# EIB64-ST4-Multi.net
KiCad netlist of a schematic drawn in EAGLE
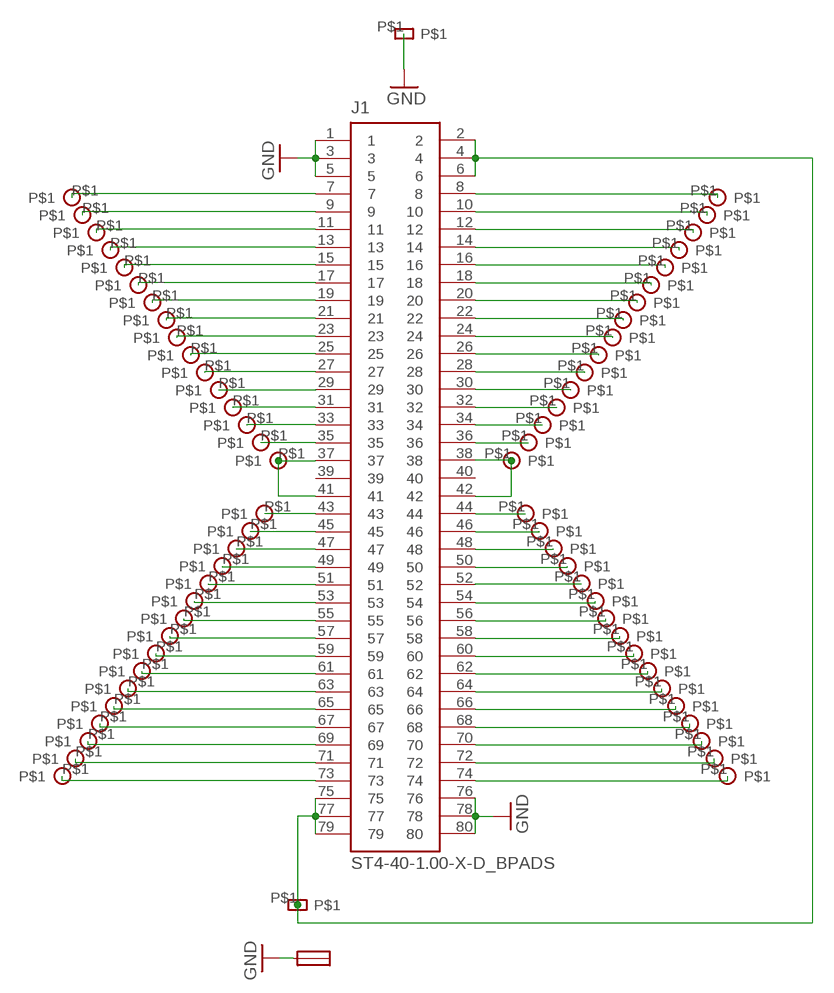
[diagram p0: schematic, sheet 1]

(export (version "E")
  (design (tool "Eeschema 10.0.6"))
  (components
    (comp (ref "J1")
      (value "ST4-40-1.00-X-D_BPADS")
      (footprint "eagle-import:ST4-40-1.00-X-D_BPADS")
      (libsource (lib "eagle-import") (part "ST4-40-1.00-X-D_BPADS"))
    )
    (comp (ref "U$1")
      (value "EIB-GND-HOLE-PAD-SMALL")
      (footprint "eagle-import:EIB-GND-HOLE-PAD-SMALL")
      (libsource (lib "eagle-import") (part "EIB-GND-HOLE-PAD-SMALL"))
    )
    (comp (ref "U$2")
      (value "JMP-PAD-SMALL")
      (footprint "eagle-import:JMP-PAD-SMALL")
      (libsource (lib "eagle-import") (part "JMP-PAD-SMALL"))
    )
    (comp (ref "U$3")
      (value "EIB-GND-HOLE-PAD-SMALL")
      (footprint "eagle-import:EIB-GND-HOLE-PAD-SMALL")
      (libsource (lib "eagle-import") (part "EIB-GND-HOLE-PAD-SMALL"))
    )
    (comp (ref "U$5")
      (value "EIB-TETRODE-HOLE-RS-PAD")
      (footprint "eagle-import:EIB-TETRODE-HOLE-RS-PAD")
      (libsource (lib "eagle-import") (part "EIB-TETRODE-HOLE-RS-PAD"))
    )
    (comp (ref "U$6")
      (value "EIB-TETRODE-HOLE-RS-PAD")
      (footprint "eagle-import:EIB-TETRODE-HOLE-RS-PAD")
      (libsource (lib "eagle-import") (part "EIB-TETRODE-HOLE-RS-PAD"))
    )
    (comp (ref "U$7")
      (value "EIB-TETRODE-HOLE-RS-PAD")
      (footprint "eagle-import:EIB-TETRODE-HOLE-RS-PAD")
      (libsource (lib "eagle-import") (part "EIB-TETRODE-HOLE-RS-PAD"))
    )
    (comp (ref "U$8")
      (value "EIB-TETRODE-HOLE-RS-PAD")
      (footprint "eagle-import:EIB-TETRODE-HOLE-RS-PAD")
      (libsource (lib "eagle-import") (part "EIB-TETRODE-HOLE-RS-PAD"))
    )
    (comp (ref "U$9")
      (value "EIB-TETRODE-HOLE-RS-PAD")
      (footprint "eagle-import:EIB-TETRODE-HOLE-RS-PAD")
      (libsource (lib "eagle-import") (part "EIB-TETRODE-HOLE-RS-PAD"))
    )
    (comp (ref "U$10")
      (value "EIB-TETRODE-HOLE-RS-PAD")
      (footprint "eagle-import:EIB-TETRODE-HOLE-RS-PAD")
      (libsource (lib "eagle-import") (part "EIB-TETRODE-HOLE-RS-PAD"))
    )
    (comp (ref "U$11")
      (value "EIB-TETRODE-HOLE-RS-PAD")
      (footprint "eagle-import:EIB-TETRODE-HOLE-RS-PAD")
      (libsource (lib "eagle-import") (part "EIB-TETRODE-HOLE-RS-PAD"))
    )
    (comp (ref "U$12")
      (value "EIB-TETRODE-HOLE-RS-PAD")
      (footprint "eagle-import:EIB-TETRODE-HOLE-RS-PAD")
      (libsource (lib "eagle-import") (part "EIB-TETRODE-HOLE-RS-PAD"))
    )
    (comp (ref "U$13")
      (value "EIB-TETRODE-HOLE-RS-PAD")
      (footprint "eagle-import:EIB-TETRODE-HOLE-RS-PAD")
      (libsource (lib "eagle-import") (part "EIB-TETRODE-HOLE-RS-PAD"))
    )
    (comp (ref "U$14")
      (value "EIB-TETRODE-HOLE-RS-PAD")
      (footprint "eagle-import:EIB-TETRODE-HOLE-RS-PAD")
      (libsource (lib "eagle-import") (part "EIB-TETRODE-HOLE-RS-PAD"))
    )
    (comp (ref "U$15")
      (value "EIB-TETRODE-HOLE-RS-PAD")
      (footprint "eagle-import:EIB-TETRODE-HOLE-RS-PAD")
      (libsource (lib "eagle-import") (part "EIB-TETRODE-HOLE-RS-PAD"))
    )
    (comp (ref "U$16")
      (value "EIB-TETRODE-HOLE-RS-PAD")
      (footprint "eagle-import:EIB-TETRODE-HOLE-RS-PAD")
      (libsource (lib "eagle-import") (part "EIB-TETRODE-HOLE-RS-PAD"))
    )
    (comp (ref "U$17")
      (value "EIB-TETRODE-HOLE-RS-PAD")
      (footprint "eagle-import:EIB-TETRODE-HOLE-RS-PAD")
      (libsource (lib "eagle-import") (part "EIB-TETRODE-HOLE-RS-PAD"))
    )
    (comp (ref "U$18")
      (value "EIB-TETRODE-HOLE-RS-PAD")
      (footprint "eagle-import:EIB-TETRODE-HOLE-RS-PAD")
      (libsource (lib "eagle-import") (part "EIB-TETRODE-HOLE-RS-PAD"))
    )
    (comp (ref "U$19")
      (value "EIB-TETRODE-HOLE-RS-PAD")
      (footprint "eagle-import:EIB-TETRODE-HOLE-RS-PAD")
      (libsource (lib "eagle-import") (part "EIB-TETRODE-HOLE-RS-PAD"))
    )
    (comp (ref "U$20")
      (value "EIB-TETRODE-HOLE-RS-PAD")
      (footprint "eagle-import:EIB-TETRODE-HOLE-RS-PAD")
      (libsource (lib "eagle-import") (part "EIB-TETRODE-HOLE-RS-PAD"))
    )
    (comp (ref "U$21")
      (value "EIB-TETRODE-HOLE-RS-PAD")
      (footprint "eagle-import:EIB-TETRODE-HOLE-RS-PAD")
      (libsource (lib "eagle-import") (part "EIB-TETRODE-HOLE-RS-PAD"))
    )
    (comp (ref "U$22")
      (value "EIB-TETRODE-HOLE-RS-PAD")
      (footprint "eagle-import:EIB-TETRODE-HOLE-RS-PAD")
      (libsource (lib "eagle-import") (part "EIB-TETRODE-HOLE-RS-PAD"))
    )
    (comp (ref "U$23")
      (value "EIB-TETRODE-HOLE-RS-PAD")
      (footprint "eagle-import:EIB-TETRODE-HOLE-RS-PAD")
      (libsource (lib "eagle-import") (part "EIB-TETRODE-HOLE-RS-PAD"))
    )
    (comp (ref "U$24")
      (value "EIB-TETRODE-HOLE-RS-PAD")
      (footprint "eagle-import:EIB-TETRODE-HOLE-RS-PAD")
      (libsource (lib "eagle-import") (part "EIB-TETRODE-HOLE-RS-PAD"))
    )
    (comp (ref "U$25")
      (value "EIB-TETRODE-HOLE-RS-PAD")
      (footprint "eagle-import:EIB-TETRODE-HOLE-RS-PAD")
      (libsource (lib "eagle-import") (part "EIB-TETRODE-HOLE-RS-PAD"))
    )
    (comp (ref "U$26")
      (value "EIB-TETRODE-HOLE-RS-PAD")
      (footprint "eagle-import:EIB-TETRODE-HOLE-RS-PAD")
      (libsource (lib "eagle-import") (part "EIB-TETRODE-HOLE-RS-PAD"))
    )
    (comp (ref "U$27")
      (value "EIB-TETRODE-HOLE-RS-PAD")
      (footprint "eagle-import:EIB-TETRODE-HOLE-RS-PAD")
      (libsource (lib "eagle-import") (part "EIB-TETRODE-HOLE-RS-PAD"))
    )
    (comp (ref "U$28")
      (value "EIB-TETRODE-HOLE-RS-PAD")
      (footprint "eagle-import:EIB-TETRODE-HOLE-RS-PAD")
      (libsource (lib "eagle-import") (part "EIB-TETRODE-HOLE-RS-PAD"))
    )
    (comp (ref "U$29")
      (value "EIB-TETRODE-HOLE-RS-PAD")
      (footprint "eagle-import:EIB-TETRODE-HOLE-RS-PAD")
      (libsource (lib "eagle-import") (part "EIB-TETRODE-HOLE-RS-PAD"))
    )
    (comp (ref "U$30")
      (value "EIB-TETRODE-HOLE-RS-PAD")
      (footprint "eagle-import:EIB-TETRODE-HOLE-RS-PAD")
      (libsource (lib "eagle-import") (part "EIB-TETRODE-HOLE-RS-PAD"))
    )
    (comp (ref "U$31")
      (value "EIB-TETRODE-HOLE-RS-PAD")
      (footprint "eagle-import:EIB-TETRODE-HOLE-RS-PAD")
      (libsource (lib "eagle-import") (part "EIB-TETRODE-HOLE-RS-PAD"))
    )
    (comp (ref "U$32")
      (value "EIB-TETRODE-HOLE-RS-PAD")
      (footprint "eagle-import:EIB-TETRODE-HOLE-RS-PAD")
      (libsource (lib "eagle-import") (part "EIB-TETRODE-HOLE-RS-PAD"))
    )
    (comp (ref "U$33")
      (value "EIB-TETRODE-HOLE-RS-PAD")
      (footprint "eagle-import:EIB-TETRODE-HOLE-RS-PAD")
      (libsource (lib "eagle-import") (part "EIB-TETRODE-HOLE-RS-PAD"))
    )
    (comp (ref "U$34")
      (value "EIB-TETRODE-HOLE-RS-PAD")
      (footprint "eagle-import:EIB-TETRODE-HOLE-RS-PAD")
      (libsource (lib "eagle-import") (part "EIB-TETRODE-HOLE-RS-PAD"))
    )
    (comp (ref "U$35")
      (value "EIB-TETRODE-HOLE-RS-PAD")
      (footprint "eagle-import:EIB-TETRODE-HOLE-RS-PAD")
      (libsource (lib "eagle-import") (part "EIB-TETRODE-HOLE-RS-PAD"))
    )
    (comp (ref "U$36")
      (value "EIB-TETRODE-HOLE-RS-PAD")
      (footprint "eagle-import:EIB-TETRODE-HOLE-RS-PAD")
      (libsource (lib "eagle-import") (part "EIB-TETRODE-HOLE-RS-PAD"))
    )
    (comp (ref "U$37")
      (value "EIB-TETRODE-HOLE-RS-PAD")
      (footprint "eagle-import:EIB-TETRODE-HOLE-RS-PAD")
      (libsource (lib "eagle-import") (part "EIB-TETRODE-HOLE-RS-PAD"))
    )
    (comp (ref "U$38")
      (value "EIB-TETRODE-HOLE-RS-PAD")
      (footprint "eagle-import:EIB-TETRODE-HOLE-RS-PAD")
      (libsource (lib "eagle-import") (part "EIB-TETRODE-HOLE-RS-PAD"))
    )
    (comp (ref "U$39")
      (value "EIB-TETRODE-HOLE-RS-PAD")
      (footprint "eagle-import:EIB-TETRODE-HOLE-RS-PAD")
      (libsource (lib "eagle-import") (part "EIB-TETRODE-HOLE-RS-PAD"))
    )
    (comp (ref "U$40")
      (value "EIB-TETRODE-HOLE-RS-PAD")
      (footprint "eagle-import:EIB-TETRODE-HOLE-RS-PAD")
      (libsource (lib "eagle-import") (part "EIB-TETRODE-HOLE-RS-PAD"))
    )
    (comp (ref "U$41")
      (value "EIB-TETRODE-HOLE-RS-PAD")
      (footprint "eagle-import:EIB-TETRODE-HOLE-RS-PAD")
      (libsource (lib "eagle-import") (part "EIB-TETRODE-HOLE-RS-PAD"))
    )
    (comp (ref "U$42")
      (value "EIB-TETRODE-HOLE-RS-PAD")
      (footprint "eagle-import:EIB-TETRODE-HOLE-RS-PAD")
      (libsource (lib "eagle-import") (part "EIB-TETRODE-HOLE-RS-PAD"))
    )
    (comp (ref "U$43")
      (value "EIB-TETRODE-HOLE-RS-PAD")
      (footprint "eagle-import:EIB-TETRODE-HOLE-RS-PAD")
      (libsource (lib "eagle-import") (part "EIB-TETRODE-HOLE-RS-PAD"))
    )
    (comp (ref "U$44")
      (value "EIB-TETRODE-HOLE-RS-PAD")
      (footprint "eagle-import:EIB-TETRODE-HOLE-RS-PAD")
      (libsource (lib "eagle-import") (part "EIB-TETRODE-HOLE-RS-PAD"))
    )
    (comp (ref "U$45")
      (value "EIB-TETRODE-HOLE-RS-PAD")
      (footprint "eagle-import:EIB-TETRODE-HOLE-RS-PAD")
      (libsource (lib "eagle-import") (part "EIB-TETRODE-HOLE-RS-PAD"))
    )
    (comp (ref "U$46")
      (value "EIB-TETRODE-HOLE-RS-PAD")
      (footprint "eagle-import:EIB-TETRODE-HOLE-RS-PAD")
      (libsource (lib "eagle-import") (part "EIB-TETRODE-HOLE-RS-PAD"))
    )
    (comp (ref "U$47")
      (value "EIB-TETRODE-HOLE-RS-PAD")
      (footprint "eagle-import:EIB-TETRODE-HOLE-RS-PAD")
      (libsource (lib "eagle-import") (part "EIB-TETRODE-HOLE-RS-PAD"))
    )
    (comp (ref "U$48")
      (value "EIB-TETRODE-HOLE-RS-PAD")
      (footprint "eagle-import:EIB-TETRODE-HOLE-RS-PAD")
      (libsource (lib "eagle-import") (part "EIB-TETRODE-HOLE-RS-PAD"))
    )
    (comp (ref "U$49")
      (value "EIB-TETRODE-HOLE-RS-PAD")
      (footprint "eagle-import:EIB-TETRODE-HOLE-RS-PAD")
      (libsource (lib "eagle-import") (part "EIB-TETRODE-HOLE-RS-PAD"))
    )
    (comp (ref "U$50")
      (value "EIB-TETRODE-HOLE-RS-PAD")
      (footprint "eagle-import:EIB-TETRODE-HOLE-RS-PAD")
      (libsource (lib "eagle-import") (part "EIB-TETRODE-HOLE-RS-PAD"))
    )
    (comp (ref "U$51")
      (value "EIB-TETRODE-HOLE-RS-PAD")
      (footprint "eagle-import:EIB-TETRODE-HOLE-RS-PAD")
      (libsource (lib "eagle-import") (part "EIB-TETRODE-HOLE-RS-PAD"))
    )
    (comp (ref "U$52")
      (value "EIB-TETRODE-HOLE-RS-PAD")
      (footprint "eagle-import:EIB-TETRODE-HOLE-RS-PAD")
      (libsource (lib "eagle-import") (part "EIB-TETRODE-HOLE-RS-PAD"))
    )
    (comp (ref "U$53")
      (value "EIB-TETRODE-HOLE-RS-PAD")
      (footprint "eagle-import:EIB-TETRODE-HOLE-RS-PAD")
      (libsource (lib "eagle-import") (part "EIB-TETRODE-HOLE-RS-PAD"))
    )
    (comp (ref "U$54")
      (value "EIB-TETRODE-HOLE-RS-PAD")
      (footprint "eagle-import:EIB-TETRODE-HOLE-RS-PAD")
      (libsource (lib "eagle-import") (part "EIB-TETRODE-HOLE-RS-PAD"))
    )
    (comp (ref "U$55")
      (value "EIB-TETRODE-HOLE-RS-PAD")
      (footprint "eagle-import:EIB-TETRODE-HOLE-RS-PAD")
      (libsource (lib "eagle-import") (part "EIB-TETRODE-HOLE-RS-PAD"))
    )
    (comp (ref "U$56")
      (value "EIB-TETRODE-HOLE-RS-PAD")
      (footprint "eagle-import:EIB-TETRODE-HOLE-RS-PAD")
      (libsource (lib "eagle-import") (part "EIB-TETRODE-HOLE-RS-PAD"))
    )
    (comp (ref "U$57")
      (value "EIB-TETRODE-HOLE-RS-PAD")
      (footprint "eagle-import:EIB-TETRODE-HOLE-RS-PAD")
      (libsource (lib "eagle-import") (part "EIB-TETRODE-HOLE-RS-PAD"))
    )
    (comp (ref "U$58")
      (value "EIB-TETRODE-HOLE-RS-PAD")
      (footprint "eagle-import:EIB-TETRODE-HOLE-RS-PAD")
      (libsource (lib "eagle-import") (part "EIB-TETRODE-HOLE-RS-PAD"))
    )
    (comp (ref "U$59")
      (value "EIB-TETRODE-HOLE-RS-PAD")
      (footprint "eagle-import:EIB-TETRODE-HOLE-RS-PAD")
      (libsource (lib "eagle-import") (part "EIB-TETRODE-HOLE-RS-PAD"))
    )
    (comp (ref "U$60")
      (value "EIB-TETRODE-HOLE-RS-PAD")
      (footprint "eagle-import:EIB-TETRODE-HOLE-RS-PAD")
      (libsource (lib "eagle-import") (part "EIB-TETRODE-HOLE-RS-PAD"))
    )
    (comp (ref "U$61")
      (value "EIB-TETRODE-HOLE-RS-PAD")
      (footprint "eagle-import:EIB-TETRODE-HOLE-RS-PAD")
      (libsource (lib "eagle-import") (part "EIB-TETRODE-HOLE-RS-PAD"))
    )
    (comp (ref "U$62")
      (value "EIB-TETRODE-HOLE-RS-PAD")
      (footprint "eagle-import:EIB-TETRODE-HOLE-RS-PAD")
      (libsource (lib "eagle-import") (part "EIB-TETRODE-HOLE-RS-PAD"))
    )
    (comp (ref "U$63")
      (value "EIB-TETRODE-HOLE-RS-PAD")
      (footprint "eagle-import:EIB-TETRODE-HOLE-RS-PAD")
      (libsource (lib "eagle-import") (part "EIB-TETRODE-HOLE-RS-PAD"))
    )
    (comp (ref "U$64")
      (value "EIB-TETRODE-HOLE-RS-PAD")
      (footprint "eagle-import:EIB-TETRODE-HOLE-RS-PAD")
      (libsource (lib "eagle-import") (part "EIB-TETRODE-HOLE-RS-PAD"))
    )
    (comp (ref "U$65")
      (value "EIB-TETRODE-HOLE-RS-PAD")
      (footprint "eagle-import:EIB-TETRODE-HOLE-RS-PAD")
      (libsource (lib "eagle-import") (part "EIB-TETRODE-HOLE-RS-PAD"))
    )
    (comp (ref "U$66")
      (value "EIB-TETRODE-HOLE-RS-PAD")
      (footprint "eagle-import:EIB-TETRODE-HOLE-RS-PAD")
      (libsource (lib "eagle-import") (part "EIB-TETRODE-HOLE-RS-PAD"))
    )
    (comp (ref "U$67")
      (value "EIB-TETRODE-HOLE-RS-PAD")
      (footprint "eagle-import:EIB-TETRODE-HOLE-RS-PAD")
      (libsource (lib "eagle-import") (part "EIB-TETRODE-HOLE-RS-PAD"))
    )
    (comp (ref "U$68")
      (value "EIB-TETRODE-HOLE-RS-PAD")
      (footprint "eagle-import:EIB-TETRODE-HOLE-RS-PAD")
      (libsource (lib "eagle-import") (part "EIB-TETRODE-HOLE-RS-PAD"))
    )
  )
  (nets
    (net (code "1") (name "GND") (class "Default")
      (node (ref "J1") (pin "1") (pinfunction "1_1") (pintype "bidirectional"))
      (node (ref "J1") (pin "3") (pinfunction "3_3") (pintype "bidirectional"))
      (node (ref "J1") (pin "5") (pinfunction "5_5") (pintype "bidirectional"))
      (node (ref "J1") (pin "76") (pinfunction "76_76") (pintype "bidirectional"))
      (node (ref "J1") (pin "78") (pinfunction "78_78") (pintype "bidirectional"))
      (node (ref "J1") (pin "80") (pinfunction "80_80") (pintype "bidirectional"))
      (node (ref "U$1") (pin "P$1") (pinfunction "P$1_P$1") (pintype "bidirectional"))
      (node (ref "U$2") (pin "P$1") (pinfunction "P$1_P$1") (pintype "bidirectional"))
    )
    (net (code "2") (name "Net-(J1-Pad2)") (class "Default")
      (node (ref "J1") (pin "2") (pinfunction "2_2") (pintype "bidirectional"))
      (node (ref "J1") (pin "4") (pinfunction "4_4") (pintype "bidirectional"))
      (node (ref "J1") (pin "6") (pinfunction "6_6") (pintype "bidirectional"))
      (node (ref "J1") (pin "75") (pinfunction "75_75") (pintype "bidirectional"))
      (node (ref "J1") (pin "77") (pinfunction "77_77") (pintype "bidirectional"))
      (node (ref "J1") (pin "79") (pinfunction "79_79") (pintype "bidirectional"))
      (node (ref "U$3") (pin "P$1") (pinfunction "P$1_P$1") (pintype "bidirectional"))
    )
    (net (code "3") (name "Net-(J1-Pad7)") (class "Default")
      (node (ref "J1") (pin "7") (pinfunction "7_7") (pintype "bidirectional"))
      (node (ref "U$36") (pin "P$1") (pinfunction "P$1_P$1") (pintype "bidirectional"))
    )
    (net (code "4") (name "Net-(J1-Pad8)") (class "Default")
      (node (ref "J1") (pin "8") (pinfunction "8_8") (pintype "bidirectional"))
      (node (ref "U$22") (pin "P$1") (pinfunction "P$1_P$1") (pintype "bidirectional"))
    )
    (net (code "5") (name "Net-(J1-Pad9)") (class "Default")
      (node (ref "J1") (pin "9") (pinfunction "9_9") (pintype "bidirectional"))
      (node (ref "U$35") (pin "P$1") (pinfunction "P$1_P$1") (pintype "bidirectional"))
    )
    (net (code "6") (name "Net-(J1-Pad10)") (class "Default")
      (node (ref "J1") (pin "10") (pinfunction "10_10") (pintype "bidirectional"))
      (node (ref "U$21") (pin "P$1") (pinfunction "P$1_P$1") (pintype "bidirectional"))
    )
    (net (code "7") (name "Net-(J1-Pad11)") (class "Default")
      (node (ref "J1") (pin "11") (pinfunction "11_11") (pintype "bidirectional"))
      (node (ref "U$34") (pin "P$1") (pinfunction "P$1_P$1") (pintype "bidirectional"))
    )
    (net (code "8") (name "Net-(J1-Pad12)") (class "Default")
      (node (ref "J1") (pin "12") (pinfunction "12_12") (pintype "bidirectional"))
      (node (ref "U$20") (pin "P$1") (pinfunction "P$1_P$1") (pintype "bidirectional"))
    )
    (net (code "9") (name "Net-(J1-Pad13)") (class "Default")
      (node (ref "J1") (pin "13") (pinfunction "13_13") (pintype "bidirectional"))
      (node (ref "U$33") (pin "P$1") (pinfunction "P$1_P$1") (pintype "bidirectional"))
    )
    (net (code "10") (name "Net-(J1-Pad14)") (class "Default")
      (node (ref "J1") (pin "14") (pinfunction "14_14") (pintype "bidirectional"))
      (node (ref "U$19") (pin "P$1") (pinfunction "P$1_P$1") (pintype "bidirectional"))
    )
    (net (code "11") (name "Net-(J1-Pad15)") (class "Default")
      (node (ref "J1") (pin "15") (pinfunction "15_15") (pintype "bidirectional"))
      (node (ref "U$32") (pin "P$1") (pinfunction "P$1_P$1") (pintype "bidirectional"))
    )
    (net (code "12") (name "Net-(J1-Pad16)") (class "Default")
      (node (ref "J1") (pin "16") (pinfunction "16_16") (pintype "bidirectional"))
      (node (ref "U$18") (pin "P$1") (pinfunction "P$1_P$1") (pintype "bidirectional"))
    )
    (net (code "13") (name "Net-(J1-Pad17)") (class "Default")
      (node (ref "J1") (pin "17") (pinfunction "17_17") (pintype "bidirectional"))
      (node (ref "U$31") (pin "P$1") (pinfunction "P$1_P$1") (pintype "bidirectional"))
    )
    (net (code "14") (name "Net-(J1-Pad18)") (class "Default")
      (node (ref "J1") (pin "18") (pinfunction "18_18") (pintype "bidirectional"))
      (node (ref "U$17") (pin "P$1") (pinfunction "P$1_P$1") (pintype "bidirectional"))
    )
    (net (code "15") (name "Net-(J1-Pad19)") (class "Default")
      (node (ref "J1") (pin "19") (pinfunction "19_19") (pintype "bidirectional"))
      (node (ref "U$30") (pin "P$1") (pinfunction "P$1_P$1") (pintype "bidirectional"))
    )
    (net (code "16") (name "Net-(J1-Pad20)") (class "Default")
      (node (ref "J1") (pin "20") (pinfunction "20_20") (pintype "bidirectional"))
      (node (ref "U$16") (pin "P$1") (pinfunction "P$1_P$1") (pintype "bidirectional"))
    )
    (net (code "17") (name "Net-(J1-Pad21)") (class "Default")
      (node (ref "J1") (pin "21") (pinfunction "21_21") (pintype "bidirectional"))
      (node (ref "U$29") (pin "P$1") (pinfunction "P$1_P$1") (pintype "bidirectional"))
    )
    (net (code "18") (name "Net-(J1-Pad22)") (class "Default")
      (node (ref "J1") (pin "22") (pinfunction "22_22") (pintype "bidirectional"))
      (node (ref "U$15") (pin "P$1") (pinfunction "P$1_P$1") (pintype "bidirectional"))
    )
    (net (code "19") (name "Net-(J1-Pad23)") (class "Default")
      (node (ref "J1") (pin "23") (pinfunction "23_23") (pintype "bidirectional"))
      (node (ref "U$28") (pin "P$1") (pinfunction "P$1_P$1") (pintype "bidirectional"))
    )
    (net (code "20") (name "Net-(J1-Pad24)") (class "Default")
      (node (ref "J1") (pin "24") (pinfunction "24_24") (pintype "bidirectional"))
      (node (ref "U$14") (pin "P$1") (pinfunction "P$1_P$1") (pintype "bidirectional"))
    )
    (net (code "21") (name "Net-(J1-Pad25)") (class "Default")
      (node (ref "J1") (pin "25") (pinfunction "25_25") (pintype "bidirectional"))
      (node (ref "U$27") (pin "P$1") (pinfunction "P$1_P$1") (pintype "bidirectional"))
    )
    (net (code "22") (name "Net-(J1-Pad26)") (class "Default")
      (node (ref "J1") (pin "26") (pinfunction "26_26") (pintype "bidirectional"))
      (node (ref "U$13") (pin "P$1") (pinfunction "P$1_P$1") (pintype "bidirectional"))
    )
    (net (code "23") (name "Net-(J1-Pad27)") (class "Default")
      (node (ref "J1") (pin "27") (pinfunction "27_27") (pintype "bidirectional"))
      (node (ref "U$26") (pin "P$1") (pinfunction "P$1_P$1") (pintype "bidirectional"))
    )
    (net (code "24") (name "Net-(J1-Pad28)") (class "Default")
      (node (ref "J1") (pin "28") (pinfunction "28_28") (pintype "bidirectional"))
      (node (ref "U$12") (pin "P$1") (pinfunction "P$1_P$1") (pintype "bidirectional"))
    )
    (net (code "25") (name "Net-(J1-Pad29)") (class "Default")
      (node (ref "J1") (pin "29") (pinfunction "29_29") (pintype "bidirectional"))
      (node (ref "U$25") (pin "P$1") (pinfunction "P$1_P$1") (pintype "bidirectional"))
    )
    (net (code "26") (name "Net-(J1-Pad30)") (class "Default")
      (node (ref "J1") (pin "30") (pinfunction "30_30") (pintype "bidirectional"))
      (node (ref "U$11") (pin "P$1") (pinfunction "P$1_P$1") (pintype "bidirectional"))
    )
    (net (code "27") (name "Net-(J1-Pad31)") (class "Default")
      (node (ref "J1") (pin "31") (pinfunction "31_31") (pintype "bidirectional"))
      (node (ref "U$24") (pin "P$1") (pinfunction "P$1_P$1") (pintype "bidirectional"))
    )
    (net (code "28") (name "Net-(J1-Pad32)") (class "Default")
      (node (ref "J1") (pin "32") (pinfunction "32_32") (pintype "bidirectional"))
      (node (ref "U$10") (pin "P$1") (pinfunction "P$1_P$1") (pintype "bidirectional"))
    )
    (net (code "29") (name "Net-(J1-Pad33)") (class "Default")
      (node (ref "J1") (pin "33") (pinfunction "33_33") (pintype "bidirectional"))
      (node (ref "U$23") (pin "P$1") (pinfunction "P$1_P$1") (pintype "bidirectional"))
    )
    (net (code "30") (name "Net-(J1-Pad34)") (class "Default")
      (node (ref "J1") (pin "34") (pinfunction "34_34") (pintype "bidirectional"))
      (node (ref "U$9") (pin "P$1") (pinfunction "P$1_P$1") (pintype "bidirectional"))
    )
    (net (code "31") (name "Net-(J1-Pad35)") (class "Default")
      (node (ref "J1") (pin "35") (pinfunction "35_35") (pintype "bidirectional"))
      (node (ref "U$7") (pin "P$1") (pinfunction "P$1_P$1") (pintype "bidirectional"))
    )
    (net (code "32") (name "Net-(J1-Pad36)") (class "Default")
      (node (ref "J1") (pin "36") (pinfunction "36_36") (pintype "bidirectional"))
      (node (ref "U$5") (pin "P$1") (pinfunction "P$1_P$1") (pintype "bidirectional"))
    )
    (net (code "33") (name "Net-(J1-Pad37)") (class "Default")
      (node (ref "J1") (pin "37") (pinfunction "37_37") (pintype "bidirectional"))
      (node (ref "J1") (pin "41") (pinfunction "41_41") (pintype "bidirectional"))
      (node (ref "U$8") (pin "P$1") (pinfunction "P$1_P$1") (pintype "bidirectional"))
    )
    (net (code "34") (name "Net-(J1-Pad38)") (class "Default")
      (node (ref "J1") (pin "38") (pinfunction "38_38") (pintype "bidirectional"))
      (node (ref "J1") (pin "42") (pinfunction "42_42") (pintype "bidirectional"))
      (node (ref "U$6") (pin "P$1") (pinfunction "P$1_P$1") (pintype "bidirectional"))
    )
    (net (code "35") (name "Net-(J1-Pad43)") (class "Default")
      (node (ref "J1") (pin "43") (pinfunction "43_43") (pintype "bidirectional"))
      (node (ref "U$53") (pin "P$1") (pinfunction "P$1_P$1") (pintype "bidirectional"))
    )
    (net (code "36") (name "Net-(J1-Pad44)") (class "Default")
      (node (ref "J1") (pin "44") (pinfunction "44_44") (pintype "bidirectional"))
      (node (ref "U$37") (pin "P$1") (pinfunction "P$1_P$1") (pintype "bidirectional"))
    )
    (net (code "37") (name "Net-(J1-Pad45)") (class "Default")
      (node (ref "J1") (pin "45") (pinfunction "45_45") (pintype "bidirectional"))
      (node (ref "U$54") (pin "P$1") (pinfunction "P$1_P$1") (pintype "bidirectional"))
    )
    (net (code "38") (name "Net-(J1-Pad46)") (class "Default")
      (node (ref "J1") (pin "46") (pinfunction "46_46") (pintype "bidirectional"))
      (node (ref "U$38") (pin "P$1") (pinfunction "P$1_P$1") (pintype "bidirectional"))
    )
    (net (code "39") (name "Net-(J1-Pad47)") (class "Default")
      (node (ref "J1") (pin "47") (pinfunction "47_47") (pintype "bidirectional"))
      (node (ref "U$55") (pin "P$1") (pinfunction "P$1_P$1") (pintype "bidirectional"))
    )
    (net (code "40") (name "Net-(J1-Pad48)") (class "Default")
      (node (ref "J1") (pin "48") (pinfunction "48_48") (pintype "bidirectional"))
      (node (ref "U$39") (pin "P$1") (pinfunction "P$1_P$1") (pintype "bidirectional"))
    )
    (net (code "41") (name "Net-(J1-Pad49)") (class "Default")
      (node (ref "J1") (pin "49") (pinfunction "49_49") (pintype "bidirectional"))
      (node (ref "U$56") (pin "P$1") (pinfunction "P$1_P$1") (pintype "bidirectional"))
    )
    (net (code "42") (name "Net-(J1-Pad50)") (class "Default")
      (node (ref "J1") (pin "50") (pinfunction "50_50") (pintype "bidirectional"))
      (node (ref "U$40") (pin "P$1") (pinfunction "P$1_P$1") (pintype "bidirectional"))
    )
    (net (code "43") (name "Net-(J1-Pad51)") (class "Default")
      (node (ref "J1") (pin "51") (pinfunction "51_51") (pintype "bidirectional"))
      (node (ref "U$57") (pin "P$1") (pinfunction "P$1_P$1") (pintype "bidirectional"))
    )
    (net (code "44") (name "Net-(J1-Pad52)") (class "Default")
      (node (ref "J1") (pin "52") (pinfunction "52_52") (pintype "bidirectional"))
      (node (ref "U$41") (pin "P$1") (pinfunction "P$1_P$1") (pintype "bidirectional"))
    )
    (net (code "45") (name "Net-(J1-Pad53)") (class "Default")
      (node (ref "J1") (pin "53") (pinfunction "53_53") (pintype "bidirectional"))
      (node (ref "U$58") (pin "P$1") (pinfunction "P$1_P$1") (pintype "bidirectional"))
    )
    (net (code "46") (name "Net-(J1-Pad54)") (class "Default")
      (node (ref "J1") (pin "54") (pinfunction "54_54") (pintype "bidirectional"))
      (node (ref "U$42") (pin "P$1") (pinfunction "P$1_P$1") (pintype "bidirectional"))
    )
    (net (code "47") (name "Net-(J1-Pad55)") (class "Default")
      (node (ref "J1") (pin "55") (pinfunction "55_55") (pintype "bidirectional"))
      (node (ref "U$59") (pin "P$1") (pinfunction "P$1_P$1") (pintype "bidirectional"))
    )
    (net (code "48") (name "Net-(J1-Pad56)") (class "Default")
      (node (ref "J1") (pin "56") (pinfunction "56_56") (pintype "bidirectional"))
      (node (ref "U$43") (pin "P$1") (pinfunction "P$1_P$1") (pintype "bidirectional"))
    )
    (net (code "49") (name "Net-(J1-Pad57)") (class "Default")
      (node (ref "J1") (pin "57") (pinfunction "57_57") (pintype "bidirectional"))
      (node (ref "U$60") (pin "P$1") (pinfunction "P$1_P$1") (pintype "bidirectional"))
    )
    (net (code "50") (name "Net-(J1-Pad58)") (class "Default")
      (node (ref "J1") (pin "58") (pinfunction "58_58") (pintype "bidirectional"))
      (node (ref "U$44") (pin "P$1") (pinfunction "P$1_P$1") (pintype "bidirectional"))
    )
    (net (code "51") (name "Net-(J1-Pad59)") (class "Default")
      (node (ref "J1") (pin "59") (pinfunction "59_59") (pintype "bidirectional"))
      (node (ref "U$61") (pin "P$1") (pinfunction "P$1_P$1") (pintype "bidirectional"))
    )
    (net (code "52") (name "Net-(J1-Pad60)") (class "Default")
      (node (ref "J1") (pin "60") (pinfunction "60_60") (pintype "bidirectional"))
      (node (ref "U$45") (pin "P$1") (pinfunction "P$1_P$1") (pintype "bidirectional"))
    )
    (net (code "53") (name "Net-(J1-Pad61)") (class "Default")
      (node (ref "J1") (pin "61") (pinfunction "61_61") (pintype "bidirectional"))
      (node (ref "U$62") (pin "P$1") (pinfunction "P$1_P$1") (pintype "bidirectional"))
    )
    (net (code "54") (name "Net-(J1-Pad62)") (class "Default")
      (node (ref "J1") (pin "62") (pinfunction "62_62") (pintype "bidirectional"))
      (node (ref "U$46") (pin "P$1") (pinfunction "P$1_P$1") (pintype "bidirectional"))
    )
    (net (code "55") (name "Net-(J1-Pad63)") (class "Default")
      (node (ref "J1") (pin "63") (pinfunction "63_63") (pintype "bidirectional"))
      (node (ref "U$63") (pin "P$1") (pinfunction "P$1_P$1") (pintype "bidirectional"))
    )
    (net (code "56") (name "Net-(J1-Pad64)") (class "Default")
      (node (ref "J1") (pin "64") (pinfunction "64_64") (pintype "bidirectional"))
      (node (ref "U$47") (pin "P$1") (pinfunction "P$1_P$1") (pintype "bidirectional"))
    )
    (net (code "57") (name "Net-(J1-Pad65)") (class "Default")
      (node (ref "J1") (pin "65") (pinfunction "65_65") (pintype "bidirectional"))
      (node (ref "U$64") (pin "P$1") (pinfunction "P$1_P$1") (pintype "bidirectional"))
    )
    (net (code "58") (name "Net-(J1-Pad66)") (class "Default")
      (node (ref "J1") (pin "66") (pinfunction "66_66") (pintype "bidirectional"))
      (node (ref "U$48") (pin "P$1") (pinfunction "P$1_P$1") (pintype "bidirectional"))
    )
    (net (code "59") (name "Net-(J1-Pad67)") (class "Default")
      (node (ref "J1") (pin "67") (pinfunction "67_67") (pintype "bidirectional"))
      (node (ref "U$65") (pin "P$1") (pinfunction "P$1_P$1") (pintype "bidirectional"))
    )
    (net (code "60") (name "Net-(J1-Pad68)") (class "Default")
      (node (ref "J1") (pin "68") (pinfunction "68_68") (pintype "bidirectional"))
      (node (ref "U$49") (pin "P$1") (pinfunction "P$1_P$1") (pintype "bidirectional"))
    )
    (net (code "61") (name "Net-(J1-Pad69)") (class "Default")
      (node (ref "J1") (pin "69") (pinfunction "69_69") (pintype "bidirectional"))
      (node (ref "U$66") (pin "P$1") (pinfunction "P$1_P$1") (pintype "bidirectional"))
    )
    (net (code "62") (name "Net-(J1-Pad70)") (class "Default")
      (node (ref "J1") (pin "70") (pinfunction "70_70") (pintype "bidirectional"))
      (node (ref "U$50") (pin "P$1") (pinfunction "P$1_P$1") (pintype "bidirectional"))
    )
    (net (code "63") (name "Net-(J1-Pad71)") (class "Default")
      (node (ref "J1") (pin "71") (pinfunction "71_71") (pintype "bidirectional"))
      (node (ref "U$67") (pin "P$1") (pinfunction "P$1_P$1") (pintype "bidirectional"))
    )
    (net (code "64") (name "Net-(J1-Pad72)") (class "Default")
      (node (ref "J1") (pin "72") (pinfunction "72_72") (pintype "bidirectional"))
      (node (ref "U$51") (pin "P$1") (pinfunction "P$1_P$1") (pintype "bidirectional"))
    )
    (net (code "65") (name "Net-(J1-Pad73)") (class "Default")
      (node (ref "J1") (pin "73") (pinfunction "73_73") (pintype "bidirectional"))
      (node (ref "U$68") (pin "P$1") (pinfunction "P$1_P$1") (pintype "bidirectional"))
    )
    (net (code "66") (name "Net-(J1-Pad74)") (class "Default")
      (node (ref "J1") (pin "74") (pinfunction "74_74") (pintype "bidirectional"))
      (node (ref "U$52") (pin "P$1") (pinfunction "P$1_P$1") (pintype "bidirectional"))
    )
    (net (code "67") (name "unconnected-(J1-Pad39)") (class "Default")
      (node (ref "J1") (pin "39") (pinfunction "39_39") (pintype "bidirectional"))
    )
    (net (code "68") (name "unconnected-(J1-Pad40)") (class "Default")
      (node (ref "J1") (pin "40") (pinfunction "40_40") (pintype "bidirectional"))
    )
  )
)
